# dbg-ram-4x8K.net
KiCad netlist of a schematic drawn in EAGLE
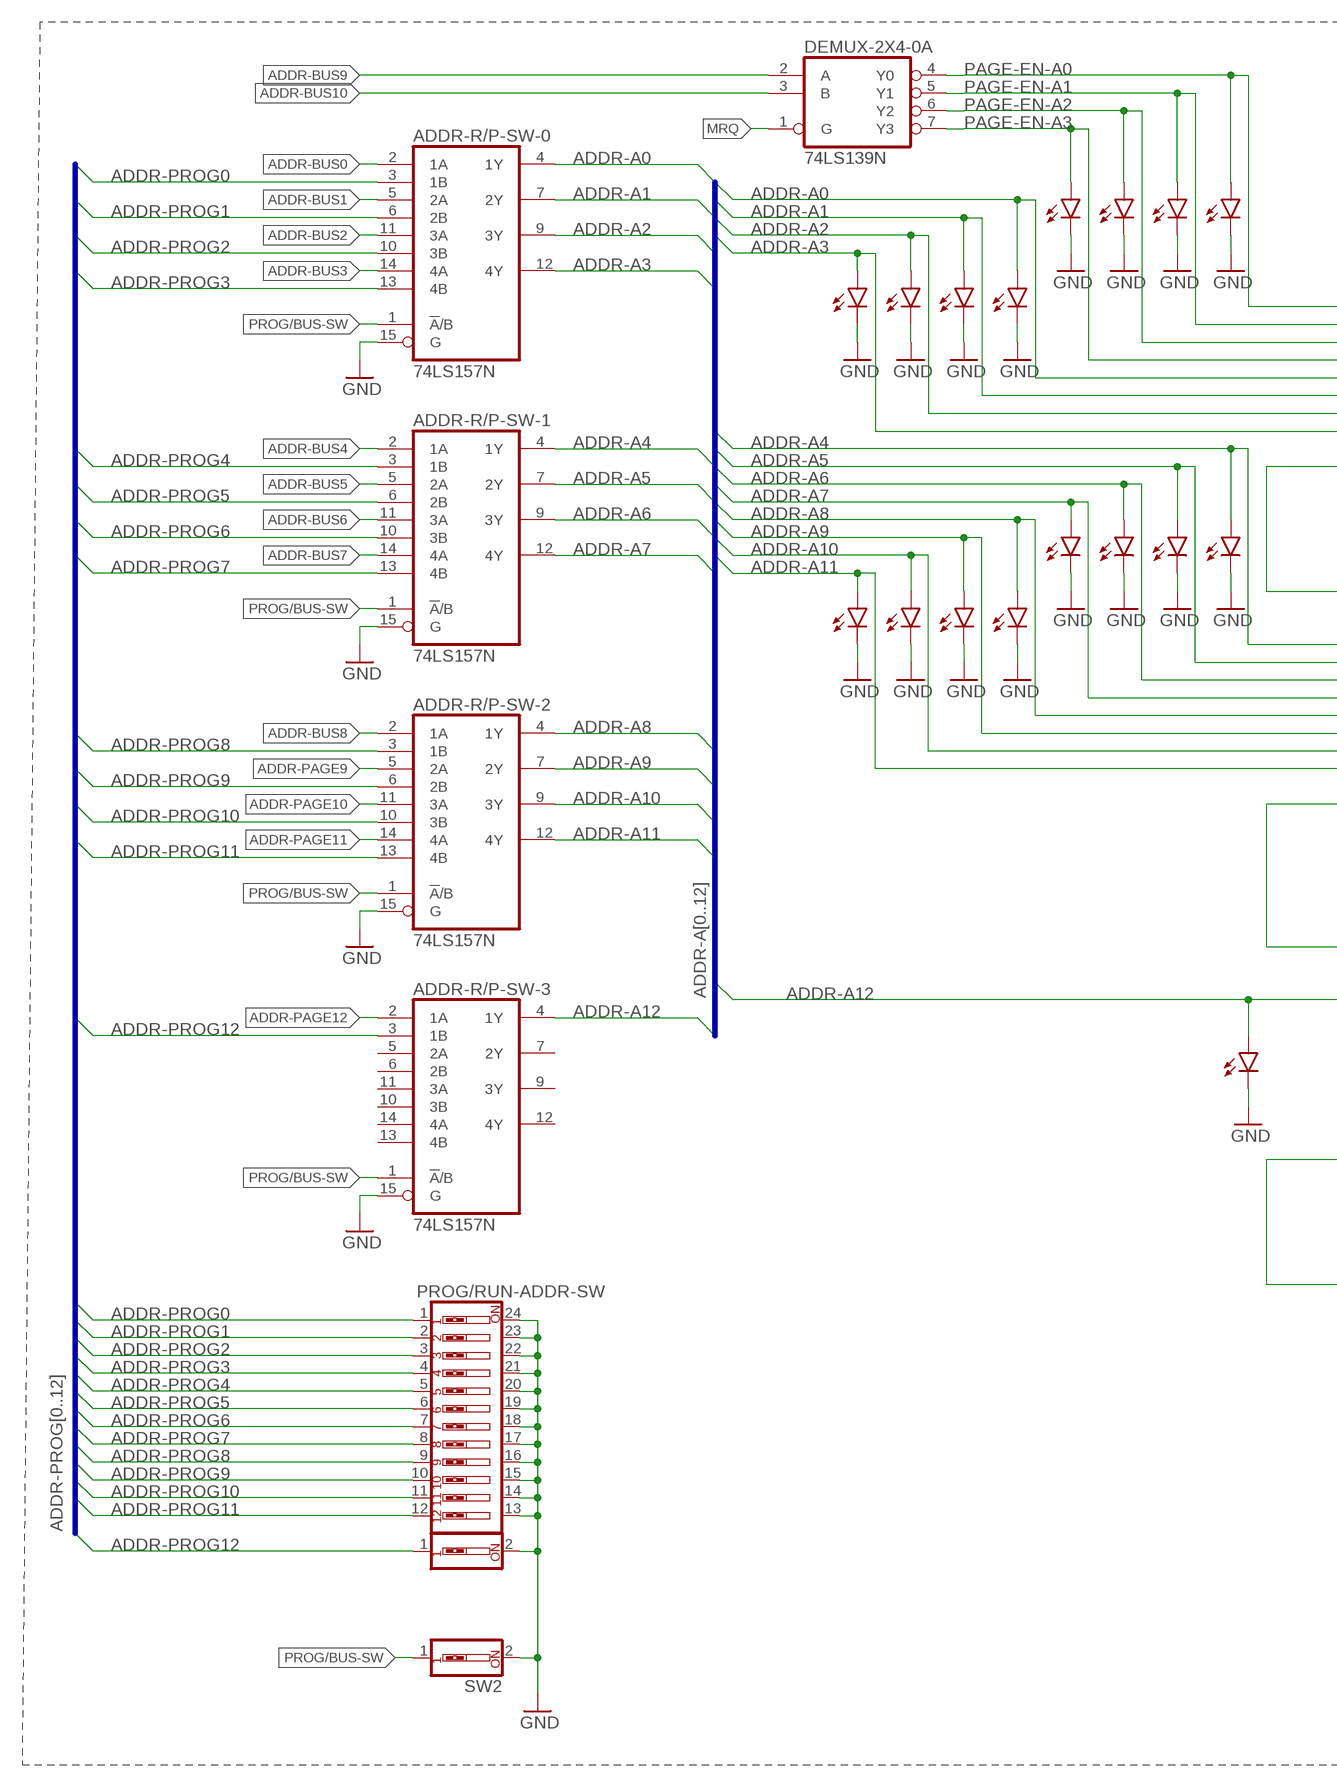
[diagram p0: schematic, sheet 1, part 1 of 2]
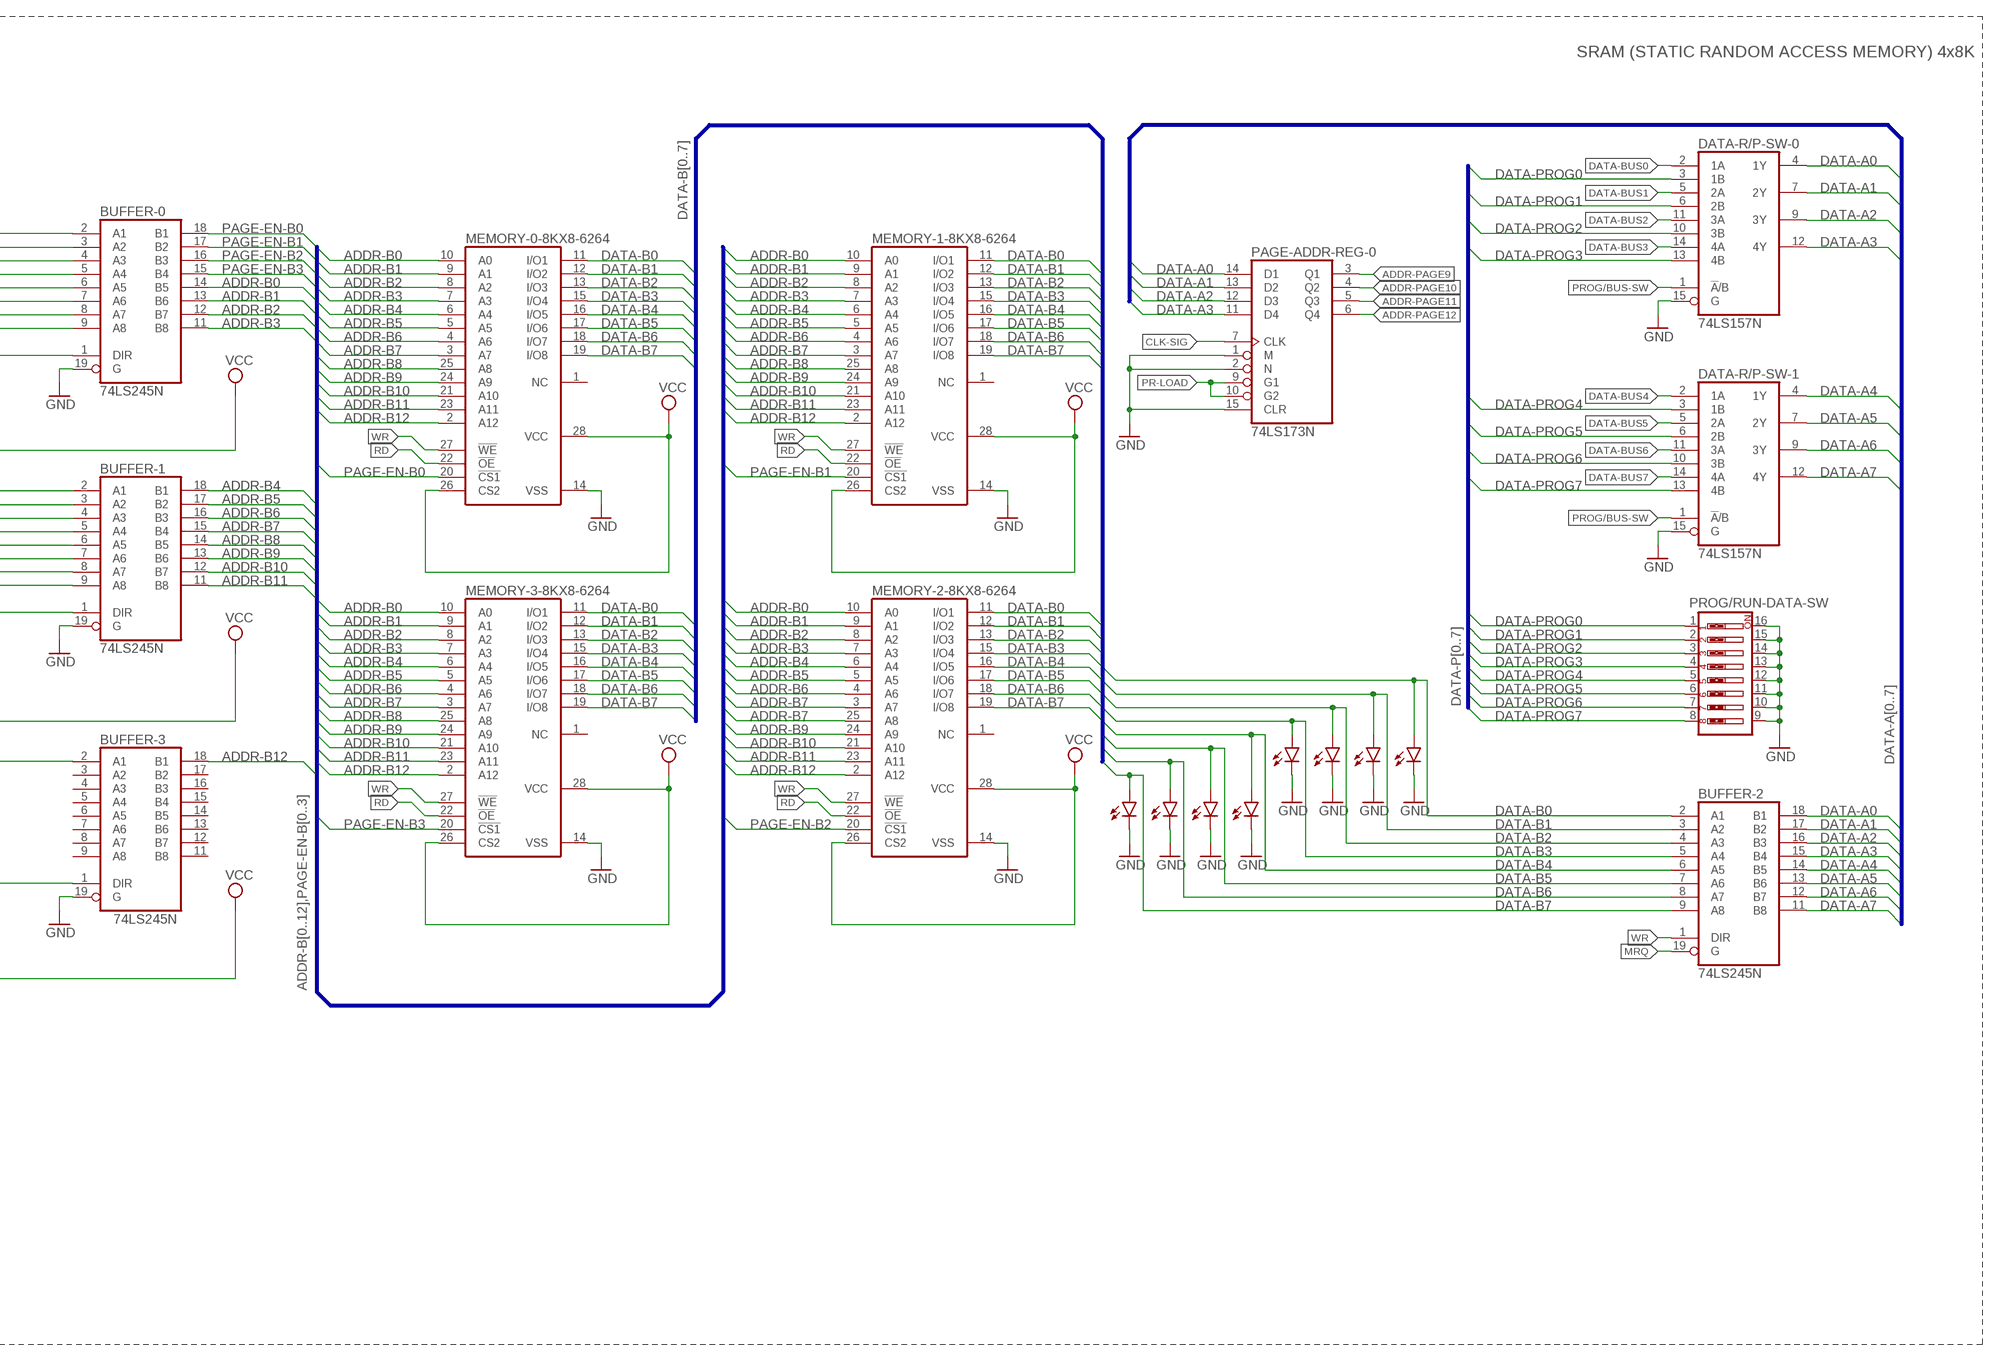
[diagram p1: schematic, sheet 1, part 2 of 2]

(export (version "E")
  (design (tool "Eeschema 10.0.6"))
  (components
    (comp (ref "ADDR-R/P-SW-0")
      (value "74LS157N")
      (footprint "eagle-import:DIL16")
      (libsource (lib "eagle-import") (part "74157NLS"))
    )
    (comp (ref "ADDR-R/P-SW-1")
      (value "74LS157N")
      (footprint "eagle-import:DIL16")
      (libsource (lib "eagle-import") (part "74157NLS"))
    )
    (comp (ref "ADDR-R/P-SW-2")
      (value "74LS157N")
      (footprint "eagle-import:DIL16")
      (libsource (lib "eagle-import") (part "74157NLS"))
    )
    (comp (ref "ADDR-R/P-SW-3")
      (value "74LS157N")
      (footprint "eagle-import:DIL16")
      (libsource (lib "eagle-import") (part "74157NLS"))
    )
    (comp (ref "BUFFER-0")
      (value "74LS245N")
      (footprint "eagle-import:DIL20")
      (libsource (lib "eagle-import") (part "74245NLS"))
    )
    (comp (ref "BUFFER-1")
      (value "74LS245N")
      (footprint "eagle-import:DIL20")
      (libsource (lib "eagle-import") (part "74245NLS"))
    )
    (comp (ref "BUFFER-2")
      (value "74LS245N")
      (footprint "eagle-import:DIL20")
      (libsource (lib "eagle-import") (part "74245NLS"))
    )
    (comp (ref "BUFFER-3")
      (value "74LS245N")
      (footprint "eagle-import:DIL20")
      (libsource (lib "eagle-import") (part "74245NLS"))
    )
    (comp (ref "DATA-R/P-SW-0")
      (value "74LS157N")
      (footprint "eagle-import:DIL16")
      (libsource (lib "eagle-import") (part "74157NLS"))
    )
    (comp (ref "DATA-R/P-SW-1")
      (value "74LS157N")
      (footprint "eagle-import:DIL16")
      (libsource (lib "eagle-import") (part "74157NLS"))
    )
    (comp (ref "DEMUX-2X4-0")
      (value "74LS139N")
      (footprint "eagle-import:DIL16")
      (libsource (lib "eagle-import") (part "74139NLS"))
    )
    (comp (ref "LED1")
      (value "LED5MM")
      (footprint "eagle-import:LED5MM")
      (libsource (lib "eagle-import") (part "LED5MM"))
    )
    (comp (ref "LED2")
      (value "LED5MM")
      (footprint "eagle-import:LED5MM")
      (libsource (lib "eagle-import") (part "LED5MM"))
    )
    (comp (ref "LED3")
      (value "LED5MM")
      (footprint "eagle-import:LED5MM")
      (libsource (lib "eagle-import") (part "LED5MM"))
    )
    (comp (ref "LED4")
      (value "LED5MM")
      (footprint "eagle-import:LED5MM")
      (libsource (lib "eagle-import") (part "LED5MM"))
    )
    (comp (ref "LED5")
      (value "LED5MM")
      (footprint "eagle-import:LED5MM")
      (libsource (lib "eagle-import") (part "LED5MM"))
    )
    (comp (ref "LED6")
      (value "LED5MM")
      (footprint "eagle-import:LED5MM")
      (libsource (lib "eagle-import") (part "LED5MM"))
    )
    (comp (ref "LED7")
      (value "LED5MM")
      (footprint "eagle-import:LED5MM")
      (libsource (lib "eagle-import") (part "LED5MM"))
    )
    (comp (ref "LED8")
      (value "LED5MM")
      (footprint "eagle-import:LED5MM")
      (libsource (lib "eagle-import") (part "LED5MM"))
    )
    (comp (ref "LED9")
      (value "LED5MM")
      (footprint "eagle-import:LED5MM")
      (libsource (lib "eagle-import") (part "LED5MM"))
    )
    (comp (ref "LED10")
      (value "LED5MM")
      (footprint "eagle-import:LED5MM")
      (libsource (lib "eagle-import") (part "LED5MM"))
    )
    (comp (ref "LED11")
      (value "LED5MM")
      (footprint "eagle-import:LED5MM")
      (libsource (lib "eagle-import") (part "LED5MM"))
    )
    (comp (ref "LED12")
      (value "LED5MM")
      (footprint "eagle-import:LED5MM")
      (libsource (lib "eagle-import") (part "LED5MM"))
    )
    (comp (ref "LED13")
      (value "LED5MM")
      (footprint "eagle-import:LED5MM")
      (libsource (lib "eagle-import") (part "LED5MM"))
    )
    (comp (ref "LED14")
      (value "LED5MM")
      (footprint "eagle-import:LED5MM")
      (libsource (lib "eagle-import") (part "LED5MM"))
    )
    (comp (ref "LED15")
      (value "LED5MM")
      (footprint "eagle-import:LED5MM")
      (libsource (lib "eagle-import") (part "LED5MM"))
    )
    (comp (ref "LED16")
      (value "LED5MM")
      (footprint "eagle-import:LED5MM")
      (libsource (lib "eagle-import") (part "LED5MM"))
    )
    (comp (ref "LED17")
      (value "LED5MM")
      (footprint "eagle-import:LED5MM")
      (libsource (lib "eagle-import") (part "LED5MM"))
    )
    (comp (ref "LED18")
      (value "LED5MM")
      (footprint "eagle-import:LED5MM")
      (libsource (lib "eagle-import") (part "LED5MM"))
    )
    (comp (ref "LED19")
      (value "LED5MM")
      (footprint "eagle-import:LED5MM")
      (libsource (lib "eagle-import") (part "LED5MM"))
    )
    (comp (ref "LED20")
      (value "LED5MM")
      (footprint "eagle-import:LED5MM")
      (libsource (lib "eagle-import") (part "LED5MM"))
    )
    (comp (ref "LED21")
      (value "LED5MM")
      (footprint "eagle-import:LED5MM")
      (libsource (lib "eagle-import") (part "LED5MM"))
    )
    (comp (ref "LED22")
      (value "LED5MM")
      (footprint "eagle-import:LED5MM")
      (libsource (lib "eagle-import") (part "LED5MM"))
    )
    (comp (ref "LED23")
      (value "LED5MM")
      (footprint "eagle-import:LED5MM")
      (libsource (lib "eagle-import") (part "LED5MM"))
    )
    (comp (ref "LED24")
      (value "LED5MM")
      (footprint "eagle-import:LED5MM")
      (libsource (lib "eagle-import") (part "LED5MM"))
    )
    (comp (ref "LED25")
      (value "LED5MM")
      (footprint "eagle-import:LED5MM")
      (libsource (lib "eagle-import") (part "LED5MM"))
    )
    (comp (ref "MEMORY-0-8KX8-6264")
      (value "6264A")
      (footprint "eagle-import:DIL28-6")
      (libsource (lib "eagle-import") (part "6264A"))
    )
    (comp (ref "MEMORY-1-8KX8-6264")
      (value "6264A")
      (footprint "eagle-import:DIL28-6")
      (libsource (lib "eagle-import") (part "6264A"))
    )
    (comp (ref "MEMORY-2-8KX8-6264")
      (value "6264A")
      (footprint "eagle-import:DIL28-6")
      (libsource (lib "eagle-import") (part "6264A"))
    )
    (comp (ref "MEMORY-3-8KX8-6264")
      (value "6264A")
      (footprint "eagle-import:DIL28-6")
      (libsource (lib "eagle-import") (part "6264A"))
    )
    (comp (ref "PAGE-ADDR-REG-0")
      (value "74LS173N")
      (footprint "eagle-import:DIL16")
      (libsource (lib "eagle-import") (part "74173NLS"))
    )
    (comp (ref "PROG/RUN-ADDR-SW")
      (value "SW_DIP-12")
      (footprint "eagle-import:EDG-12")
      (libsource (lib "eagle-import") (part "SW_DIP-12"))
    )
    (comp (ref "PROG/RUN-DATA-SW")
      (value "SW_DIP-8")
      (footprint "eagle-import:EDG-08")
      (libsource (lib "eagle-import") (part "SW_DIP-8"))
    )
    (comp (ref "SW2")
      (value "SW_DIP-1")
      (footprint "eagle-import:EDG-01")
      (libsource (lib "eagle-import") (part "SW_DIP-1"))
    )
    (comp (ref "SW3")
      (value "SW_DIP-1")
      (footprint "eagle-import:EDG-01")
      (libsource (lib "eagle-import") (part "SW_DIP-1"))
    )
  )
  (nets
    (net (code "9") (name "/ADDR-A0") (class "Default")
      (node (ref "ADDR-R/P-SW-0") (pin "4") (pinfunction "1Y_4") (pintype "output"))
      (node (ref "BUFFER-0") (pin "6") (pinfunction "A5_6") (pintype "bidirectional"))
      (node (ref "LED1") (pin "A") (pinfunction "A_A") (pintype "passive"))
    )
    (net (code "10") (name "/ADDR-A1") (class "Default")
      (node (ref "ADDR-R/P-SW-0") (pin "7") (pinfunction "2Y_7") (pintype "output"))
      (node (ref "BUFFER-0") (pin "7") (pinfunction "A6_7") (pintype "bidirectional"))
      (node (ref "LED2") (pin "A") (pinfunction "A_A") (pintype "passive"))
    )
    (net (code "11") (name "/ADDR-A2") (class "Default")
      (node (ref "ADDR-R/P-SW-0") (pin "9") (pinfunction "3Y_9") (pintype "output"))
      (node (ref "BUFFER-0") (pin "8") (pinfunction "A7_8") (pintype "bidirectional"))
      (node (ref "LED3") (pin "A") (pinfunction "A_A") (pintype "passive"))
    )
    (net (code "12") (name "/ADDR-A3") (class "Default")
      (node (ref "ADDR-R/P-SW-0") (pin "12") (pinfunction "4Y_12") (pintype "output"))
      (node (ref "BUFFER-0") (pin "9") (pinfunction "A8_9") (pintype "bidirectional"))
      (node (ref "LED4") (pin "A") (pinfunction "A_A") (pintype "passive"))
    )
    (net (code "13") (name "/ADDR-A4") (class "Default")
      (node (ref "ADDR-R/P-SW-1") (pin "4") (pinfunction "1Y_4") (pintype "output"))
      (node (ref "BUFFER-1") (pin "2") (pinfunction "A1_2") (pintype "bidirectional"))
      (node (ref "LED5") (pin "A") (pinfunction "A_A") (pintype "passive"))
    )
    (net (code "14") (name "/ADDR-A5") (class "Default")
      (node (ref "ADDR-R/P-SW-1") (pin "7") (pinfunction "2Y_7") (pintype "output"))
      (node (ref "BUFFER-1") (pin "3") (pinfunction "A2_3") (pintype "bidirectional"))
      (node (ref "LED6") (pin "A") (pinfunction "A_A") (pintype "passive"))
    )
    (net (code "15") (name "/ADDR-A6") (class "Default")
      (node (ref "ADDR-R/P-SW-1") (pin "9") (pinfunction "3Y_9") (pintype "output"))
      (node (ref "BUFFER-1") (pin "4") (pinfunction "A3_4") (pintype "bidirectional"))
      (node (ref "LED10") (pin "A") (pinfunction "A_A") (pintype "passive"))
    )
    (net (code "16") (name "/ADDR-A7") (class "Default")
      (node (ref "ADDR-R/P-SW-1") (pin "12") (pinfunction "4Y_12") (pintype "output"))
      (node (ref "BUFFER-1") (pin "5") (pinfunction "A4_5") (pintype "bidirectional"))
      (node (ref "LED7") (pin "A") (pinfunction "A_A") (pintype "passive"))
    )
    (net (code "17") (name "/ADDR-A8") (class "Default")
      (node (ref "ADDR-R/P-SW-2") (pin "4") (pinfunction "1Y_4") (pintype "output"))
      (node (ref "BUFFER-1") (pin "6") (pinfunction "A5_6") (pintype "bidirectional"))
      (node (ref "LED8") (pin "A") (pinfunction "A_A") (pintype "passive"))
    )
    (net (code "18") (name "/ADDR-A9") (class "Default")
      (node (ref "ADDR-R/P-SW-2") (pin "7") (pinfunction "2Y_7") (pintype "output"))
      (node (ref "BUFFER-1") (pin "7") (pinfunction "A6_7") (pintype "bidirectional"))
      (node (ref "LED9") (pin "A") (pinfunction "A_A") (pintype "passive"))
    )
    (net (code "19") (name "/ADDR-A10") (class "Default")
      (node (ref "ADDR-R/P-SW-2") (pin "9") (pinfunction "3Y_9") (pintype "output"))
      (node (ref "BUFFER-1") (pin "8") (pinfunction "A7_8") (pintype "bidirectional"))
      (node (ref "LED15") (pin "A") (pinfunction "A_A") (pintype "passive"))
    )
    (net (code "20") (name "/ADDR-A11") (class "Default")
      (node (ref "ADDR-R/P-SW-2") (pin "12") (pinfunction "4Y_12") (pintype "output"))
      (node (ref "BUFFER-1") (pin "9") (pinfunction "A8_9") (pintype "bidirectional"))
      (node (ref "LED17") (pin "A") (pinfunction "A_A") (pintype "passive"))
    )
    (net (code "21") (name "/ADDR-A12") (class "Default")
      (node (ref "ADDR-R/P-SW-3") (pin "4") (pinfunction "1Y_4") (pintype "output"))
      (node (ref "BUFFER-3") (pin "2") (pinfunction "A1_2") (pintype "bidirectional"))
      (node (ref "LED16") (pin "A") (pinfunction "A_A") (pintype "passive"))
    )
    (net (code "23") (name "/ADDR-B0") (class "Default")
      (node (ref "BUFFER-0") (pin "14") (pinfunction "B5_14") (pintype "bidirectional"))
      (node (ref "MEMORY-0-8KX8-6264") (pin "10") (pinfunction "A0_10") (pintype "input"))
      (node (ref "MEMORY-1-8KX8-6264") (pin "10") (pinfunction "A0_10") (pintype "input"))
      (node (ref "MEMORY-2-8KX8-6264") (pin "10") (pinfunction "A0_10") (pintype "input"))
      (node (ref "MEMORY-3-8KX8-6264") (pin "10") (pinfunction "A0_10") (pintype "input"))
    )
    (net (code "24") (name "/ADDR-B1") (class "Default")
      (node (ref "BUFFER-0") (pin "13") (pinfunction "B6_13") (pintype "bidirectional"))
      (node (ref "MEMORY-0-8KX8-6264") (pin "9") (pinfunction "A1_9") (pintype "input"))
      (node (ref "MEMORY-1-8KX8-6264") (pin "9") (pinfunction "A1_9") (pintype "input"))
      (node (ref "MEMORY-2-8KX8-6264") (pin "9") (pinfunction "A1_9") (pintype "input"))
      (node (ref "MEMORY-3-8KX8-6264") (pin "9") (pinfunction "A1_9") (pintype "input"))
    )
    (net (code "25") (name "/ADDR-B2") (class "Default")
      (node (ref "BUFFER-0") (pin "12") (pinfunction "B7_12") (pintype "bidirectional"))
      (node (ref "MEMORY-0-8KX8-6264") (pin "8") (pinfunction "A2_8") (pintype "input"))
      (node (ref "MEMORY-1-8KX8-6264") (pin "8") (pinfunction "A2_8") (pintype "input"))
      (node (ref "MEMORY-2-8KX8-6264") (pin "8") (pinfunction "A2_8") (pintype "input"))
      (node (ref "MEMORY-3-8KX8-6264") (pin "8") (pinfunction "A2_8") (pintype "input"))
    )
    (net (code "26") (name "/ADDR-B3") (class "Default")
      (node (ref "BUFFER-0") (pin "11") (pinfunction "B8_11") (pintype "bidirectional"))
      (node (ref "MEMORY-0-8KX8-6264") (pin "7") (pinfunction "A3_7") (pintype "input"))
      (node (ref "MEMORY-1-8KX8-6264") (pin "7") (pinfunction "A3_7") (pintype "input"))
      (node (ref "MEMORY-2-8KX8-6264") (pin "7") (pinfunction "A3_7") (pintype "input"))
      (node (ref "MEMORY-3-8KX8-6264") (pin "7") (pinfunction "A3_7") (pintype "input"))
    )
    (net (code "27") (name "/ADDR-B4") (class "Default")
      (node (ref "BUFFER-1") (pin "18") (pinfunction "B1_18") (pintype "bidirectional"))
      (node (ref "MEMORY-0-8KX8-6264") (pin "6") (pinfunction "A4_6") (pintype "input"))
      (node (ref "MEMORY-1-8KX8-6264") (pin "6") (pinfunction "A4_6") (pintype "input"))
      (node (ref "MEMORY-2-8KX8-6264") (pin "6") (pinfunction "A4_6") (pintype "input"))
      (node (ref "MEMORY-3-8KX8-6264") (pin "6") (pinfunction "A4_6") (pintype "input"))
    )
    (net (code "28") (name "/ADDR-B5") (class "Default")
      (node (ref "BUFFER-1") (pin "17") (pinfunction "B2_17") (pintype "bidirectional"))
      (node (ref "MEMORY-0-8KX8-6264") (pin "5") (pinfunction "A5_5") (pintype "input"))
      (node (ref "MEMORY-1-8KX8-6264") (pin "5") (pinfunction "A5_5") (pintype "input"))
      (node (ref "MEMORY-2-8KX8-6264") (pin "5") (pinfunction "A5_5") (pintype "input"))
      (node (ref "MEMORY-3-8KX8-6264") (pin "5") (pinfunction "A5_5") (pintype "input"))
    )
    (net (code "29") (name "/ADDR-B6") (class "Default")
      (node (ref "BUFFER-1") (pin "16") (pinfunction "B3_16") (pintype "bidirectional"))
      (node (ref "MEMORY-0-8KX8-6264") (pin "4") (pinfunction "A6_4") (pintype "input"))
      (node (ref "MEMORY-1-8KX8-6264") (pin "4") (pinfunction "A6_4") (pintype "input"))
      (node (ref "MEMORY-2-8KX8-6264") (pin "4") (pinfunction "A6_4") (pintype "input"))
      (node (ref "MEMORY-3-8KX8-6264") (pin "4") (pinfunction "A6_4") (pintype "input"))
    )
    (net (code "30") (name "/ADDR-B7") (class "Default")
      (node (ref "BUFFER-1") (pin "15") (pinfunction "B4_15") (pintype "bidirectional"))
      (node (ref "MEMORY-0-8KX8-6264") (pin "3") (pinfunction "A7_3") (pintype "input"))
      (node (ref "MEMORY-1-8KX8-6264") (pin "3") (pinfunction "A7_3") (pintype "input"))
      (node (ref "MEMORY-2-8KX8-6264") (pin "25") (pinfunction "A8_25") (pintype "input"))
      (node (ref "MEMORY-2-8KX8-6264") (pin "3") (pinfunction "A7_3") (pintype "input"))
      (node (ref "MEMORY-3-8KX8-6264") (pin "3") (pinfunction "A7_3") (pintype "input"))
    )
    (net (code "31") (name "/ADDR-B8") (class "Default")
      (node (ref "BUFFER-1") (pin "14") (pinfunction "B5_14") (pintype "bidirectional"))
      (node (ref "MEMORY-0-8KX8-6264") (pin "25") (pinfunction "A8_25") (pintype "input"))
      (node (ref "MEMORY-1-8KX8-6264") (pin "25") (pinfunction "A8_25") (pintype "input"))
      (node (ref "MEMORY-3-8KX8-6264") (pin "25") (pinfunction "A8_25") (pintype "input"))
    )
    (net (code "32") (name "/ADDR-B9") (class "Default")
      (node (ref "BUFFER-1") (pin "13") (pinfunction "B6_13") (pintype "bidirectional"))
      (node (ref "MEMORY-0-8KX8-6264") (pin "24") (pinfunction "A9_24") (pintype "input"))
      (node (ref "MEMORY-1-8KX8-6264") (pin "24") (pinfunction "A9_24") (pintype "input"))
      (node (ref "MEMORY-2-8KX8-6264") (pin "24") (pinfunction "A9_24") (pintype "input"))
      (node (ref "MEMORY-3-8KX8-6264") (pin "24") (pinfunction "A9_24") (pintype "input"))
    )
    (net (code "33") (name "/ADDR-B10") (class "Default")
      (node (ref "BUFFER-1") (pin "12") (pinfunction "B7_12") (pintype "bidirectional"))
      (node (ref "MEMORY-0-8KX8-6264") (pin "21") (pinfunction "A10_21") (pintype "input"))
      (node (ref "MEMORY-1-8KX8-6264") (pin "21") (pinfunction "A10_21") (pintype "input"))
      (node (ref "MEMORY-2-8KX8-6264") (pin "21") (pinfunction "A10_21") (pintype "input"))
      (node (ref "MEMORY-3-8KX8-6264") (pin "21") (pinfunction "A10_21") (pintype "input"))
    )
    (net (code "34") (name "/ADDR-B11") (class "Default")
      (node (ref "BUFFER-1") (pin "11") (pinfunction "B8_11") (pintype "bidirectional"))
      (node (ref "MEMORY-0-8KX8-6264") (pin "23") (pinfunction "A11_23") (pintype "input"))
      (node (ref "MEMORY-1-8KX8-6264") (pin "23") (pinfunction "A11_23") (pintype "input"))
      (node (ref "MEMORY-2-8KX8-6264") (pin "23") (pinfunction "A11_23") (pintype "input"))
      (node (ref "MEMORY-3-8KX8-6264") (pin "23") (pinfunction "A11_23") (pintype "input"))
    )
    (net (code "35") (name "/ADDR-B12") (class "Default")
      (node (ref "BUFFER-3") (pin "18") (pinfunction "B1_18") (pintype "bidirectional"))
      (node (ref "MEMORY-0-8KX8-6264") (pin "2") (pinfunction "A12_2") (pintype "input"))
      (node (ref "MEMORY-1-8KX8-6264") (pin "2") (pinfunction "A12_2") (pintype "input"))
      (node (ref "MEMORY-2-8KX8-6264") (pin "2") (pinfunction "A12_2") (pintype "input"))
      (node (ref "MEMORY-3-8KX8-6264") (pin "2") (pinfunction "A12_2") (pintype "input"))
    )
    (net (code "36") (name "/ADDR-PROG0") (class "Default")
      (node (ref "ADDR-R/P-SW-0") (pin "3") (pinfunction "1B_3") (pintype "input"))
      (node (ref "PROG/RUN-ADDR-SW") (pin "1") (pinfunction "1_1") (pintype "passive"))
    )
    (net (code "37") (name "/ADDR-PROG1") (class "Default")
      (node (ref "ADDR-R/P-SW-0") (pin "6") (pinfunction "2B_6") (pintype "input"))
      (node (ref "PROG/RUN-ADDR-SW") (pin "2") (pinfunction "2_2") (pintype "passive"))
    )
    (net (code "38") (name "/ADDR-PROG2") (class "Default")
      (node (ref "ADDR-R/P-SW-0") (pin "10") (pinfunction "3B_10") (pintype "input"))
      (node (ref "PROG/RUN-ADDR-SW") (pin "3") (pinfunction "3_3") (pintype "passive"))
    )
    (net (code "39") (name "/ADDR-PROG3") (class "Default")
      (node (ref "ADDR-R/P-SW-0") (pin "13") (pinfunction "4B_13") (pintype "input"))
      (node (ref "PROG/RUN-ADDR-SW") (pin "4") (pinfunction "4_4") (pintype "passive"))
    )
    (net (code "40") (name "/ADDR-PROG4") (class "Default")
      (node (ref "ADDR-R/P-SW-1") (pin "3") (pinfunction "1B_3") (pintype "input"))
      (node (ref "PROG/RUN-ADDR-SW") (pin "5") (pinfunction "5_5") (pintype "passive"))
    )
    (net (code "41") (name "/ADDR-PROG5") (class "Default")
      (node (ref "ADDR-R/P-SW-1") (pin "6") (pinfunction "2B_6") (pintype "input"))
      (node (ref "PROG/RUN-ADDR-SW") (pin "6") (pinfunction "6_6") (pintype "passive"))
    )
    (net (code "42") (name "/ADDR-PROG6") (class "Default")
      (node (ref "ADDR-R/P-SW-1") (pin "10") (pinfunction "3B_10") (pintype "input"))
      (node (ref "PROG/RUN-ADDR-SW") (pin "7") (pinfunction "7_7") (pintype "passive"))
    )
    (net (code "43") (name "/ADDR-PROG7") (class "Default")
      (node (ref "ADDR-R/P-SW-1") (pin "13") (pinfunction "4B_13") (pintype "input"))
      (node (ref "PROG/RUN-ADDR-SW") (pin "8") (pinfunction "8_8") (pintype "passive"))
    )
    (net (code "44") (name "/ADDR-PROG8") (class "Default")
      (node (ref "ADDR-R/P-SW-2") (pin "3") (pinfunction "1B_3") (pintype "input"))
      (node (ref "PROG/RUN-ADDR-SW") (pin "9") (pinfunction "9_9") (pintype "passive"))
    )
    (net (code "45") (name "/ADDR-PROG9") (class "Default")
      (node (ref "ADDR-R/P-SW-2") (pin "6") (pinfunction "2B_6") (pintype "input"))
      (node (ref "PROG/RUN-ADDR-SW") (pin "10") (pinfunction "10_10") (pintype "passive"))
    )
    (net (code "46") (name "/ADDR-PROG10") (class "Default")
      (node (ref "ADDR-R/P-SW-2") (pin "10") (pinfunction "3B_10") (pintype "input"))
      (node (ref "PROG/RUN-ADDR-SW") (pin "11") (pinfunction "11_11") (pintype "passive"))
    )
    (net (code "47") (name "/ADDR-PROG11") (class "Default")
      (node (ref "ADDR-R/P-SW-2") (pin "13") (pinfunction "4B_13") (pintype "input"))
      (node (ref "PROG/RUN-ADDR-SW") (pin "12") (pinfunction "12_12") (pintype "passive"))
    )
    (net (code "48") (name "/ADDR-PROG12") (class "Default")
      (node (ref "ADDR-R/P-SW-3") (pin "3") (pinfunction "1B_3") (pintype "input"))
      (node (ref "SW3") (pin "1") (pinfunction "1_1") (pintype "passive"))
    )
    (net (code "50") (name "/DATA-A0") (class "Default")
      (node (ref "BUFFER-2") (pin "18") (pinfunction "B1_18") (pintype "bidirectional"))
      (node (ref "DATA-R/P-SW-0") (pin "4") (pinfunction "1Y_4") (pintype "output"))
      (node (ref "PAGE-ADDR-REG-0") (pin "14") (pinfunction "D1_14") (pintype "input"))
    )
    (net (code "51") (name "/DATA-A1") (class "Default")
      (node (ref "BUFFER-2") (pin "17") (pinfunction "B2_17") (pintype "bidirectional"))
      (node (ref "DATA-R/P-SW-0") (pin "7") (pinfunction "2Y_7") (pintype "output"))
      (node (ref "PAGE-ADDR-REG-0") (pin "13") (pinfunction "D2_13") (pintype "input"))
    )
    (net (code "52") (name "/DATA-A2") (class "Default")
      (node (ref "BUFFER-2") (pin "16") (pinfunction "B3_16") (pintype "bidirectional"))
      (node (ref "DATA-R/P-SW-0") (pin "9") (pinfunction "3Y_9") (pintype "output"))
      (node (ref "PAGE-ADDR-REG-0") (pin "12") (pinfunction "D3_12") (pintype "input"))
    )
    (net (code "53") (name "/DATA-A3") (class "Default")
      (node (ref "BUFFER-2") (pin "15") (pinfunction "B4_15") (pintype "bidirectional"))
      (node (ref "DATA-R/P-SW-0") (pin "12") (pinfunction "4Y_12") (pintype "output"))
      (node (ref "PAGE-ADDR-REG-0") (pin "11") (pinfunction "D4_11") (pintype "input"))
    )
    (net (code "54") (name "/DATA-A4") (class "Default")
      (node (ref "BUFFER-2") (pin "14") (pinfunction "B5_14") (pintype "bidirectional"))
      (node (ref "DATA-R/P-SW-1") (pin "4") (pinfunction "1Y_4") (pintype "output"))
    )
    (net (code "55") (name "/DATA-A5") (class "Default")
      (node (ref "BUFFER-2") (pin "13") (pinfunction "B6_13") (pintype "bidirectional"))
      (node (ref "DATA-R/P-SW-1") (pin "7") (pinfunction "2Y_7") (pintype "output"))
    )
    (net (code "56") (name "/DATA-A6") (class "Default")
      (node (ref "BUFFER-2") (pin "12") (pinfunction "B7_12") (pintype "bidirectional"))
      (node (ref "DATA-R/P-SW-1") (pin "9") (pinfunction "3Y_9") (pintype "output"))
    )
    (net (code "57") (name "/DATA-A7") (class "Default")
      (node (ref "BUFFER-2") (pin "11") (pinfunction "B8_11") (pintype "bidirectional"))
      (node (ref "DATA-R/P-SW-1") (pin "12") (pinfunction "4Y_12") (pintype "output"))
    )
    (net (code "59") (name "/DATA-B0") (class "Default")
      (node (ref "BUFFER-2") (pin "2") (pinfunction "A1_2") (pintype "bidirectional"))
      (node (ref "LED25") (pin "A") (pinfunction "A_A") (pintype "passive"))
      (node (ref "MEMORY-0-8KX8-6264") (pin "11") (pinfunction "I/O1_11") (pintype "bidirectional"))
      (node (ref "MEMORY-1-8KX8-6264") (pin "11") (pinfunction "I/O1_11") (pintype "bidirectional"))
      (node (ref "MEMORY-2-8KX8-6264") (pin "11") (pinfunction "I/O1_11") (pintype "bidirectional"))
      (node (ref "MEMORY-3-8KX8-6264") (pin "11") (pinfunction "I/O1_11") (pintype "bidirectional"))
    )
    (net (code "60") (name "/DATA-B1") (class "Default")
      (node (ref "BUFFER-2") (pin "3") (pinfunction "A2_3") (pintype "bidirectional"))
      (node (ref "LED24") (pin "A") (pinfunction "A_A") (pintype "passive"))
      (node (ref "MEMORY-0-8KX8-6264") (pin "12") (pinfunction "I/O2_12") (pintype "bidirectional"))
      (node (ref "MEMORY-1-8KX8-6264") (pin "12") (pinfunction "I/O2_12") (pintype "bidirectional"))
      (node (ref "MEMORY-2-8KX8-6264") (pin "12") (pinfunction "I/O2_12") (pintype "bidirectional"))
      (node (ref "MEMORY-3-8KX8-6264") (pin "12") (pinfunction "I/O2_12") (pintype "bidirectional"))
    )
    (net (code "61") (name "/DATA-B2") (class "Default")
      (node (ref "BUFFER-2") (pin "4") (pinfunction "A3_4") (pintype "bidirectional"))
      (node (ref "LED23") (pin "A") (pinfunction "A_A") (pintype "passive"))
      (node (ref "MEMORY-0-8KX8-6264") (pin "13") (pinfunction "I/O3_13") (pintype "bidirectional"))
      (node (ref "MEMORY-1-8KX8-6264") (pin "13") (pinfunction "I/O3_13") (pintype "bidirectional"))
      (node (ref "MEMORY-2-8KX8-6264") (pin "13") (pinfunction "I/O3_13") (pintype "bidirectional"))
      (node (ref "MEMORY-3-8KX8-6264") (pin "13") (pinfunction "I/O3_13") (pintype "bidirectional"))
    )
    (net (code "62") (name "/DATA-B3") (class "Default")
      (node (ref "BUFFER-2") (pin "5") (pinfunction "A4_5") (pintype "bidirectional"))
      (node (ref "LED22") (pin "A") (pinfunction "A_A") (pintype "passive"))
      (node (ref "MEMORY-0-8KX8-6264") (pin "15") (pinfunction "I/O4_15") (pintype "bidirectional"))
      (node (ref "MEMORY-1-8KX8-6264") (pin "15") (pinfunction "I/O4_15") (pintype "bidirectional"))
      (node (ref "MEMORY-2-8KX8-6264") (pin "15") (pinfunction "I/O4_15") (pintype "bidirectional"))
      (node (ref "MEMORY-3-8KX8-6264") (pin "15") (pinfunction "I/O4_15") (pintype "bidirectional"))
    )
    (net (code "63") (name "/DATA-B4") (class "Default")
      (node (ref "BUFFER-2") (pin "6") (pinfunction "A5_6") (pintype "bidirectional"))
      (node (ref "LED21") (pin "A") (pinfunction "A_A") (pintype "passive"))
      (node (ref "MEMORY-0-8KX8-6264") (pin "16") (pinfunction "I/O5_16") (pintype "bidirectional"))
      (node (ref "MEMORY-1-8KX8-6264") (pin "16") (pinfunction "I/O5_16") (pintype "bidirectional"))
      (node (ref "MEMORY-2-8KX8-6264") (pin "16") (pinfunction "I/O5_16") (pintype "bidirectional"))
      (node (ref "MEMORY-3-8KX8-6264") (pin "16") (pinfunction "I/O5_16") (pintype "bidirectional"))
    )
    (net (code "64") (name "/DATA-B5") (class "Default")
      (node (ref "BUFFER-2") (pin "7") (pinfunction "A6_7") (pintype "bidirectional"))
      (node (ref "LED20") (pin "A") (pinfunction "A_A") (pintype "passive"))
      (node (ref "MEMORY-0-8KX8-6264") (pin "17") (pinfunction "I/O6_17") (pintype "bidirectional"))
      (node (ref "MEMORY-1-8KX8-6264") (pin "17") (pinfunction "I/O6_17") (pintype "bidirectional"))
      (node (ref "MEMORY-2-8KX8-6264") (pin "17") (pinfunction "I/O6_17") (pintype "bidirectional"))
      (node (ref "MEMORY-3-8KX8-6264") (pin "17") (pinfunction "I/O6_17") (pintype "bidirectional"))
    )
    (net (code "65") (name "/DATA-B6") (class "Default")
      (node (ref "BUFFER-2") (pin "8") (pinfunction "A7_8") (pintype "bidirectional"))
      (node (ref "LED19") (pin "A") (pinfunction "A_A") (pintype "passive"))
      (node (ref "MEMORY-0-8KX8-6264") (pin "18") (pinfunction "I/O7_18") (pintype "bidirectional"))
      (node (ref "MEMORY-1-8KX8-6264") (pin "18") (pinfunction "I/O7_18") (pintype "bidirectional"))
      (node (ref "MEMORY-2-8KX8-6264") (pin "18") (pinfunction "I/O7_18") (pintype "bidirectional"))
      (node (ref "MEMORY-3-8KX8-6264") (pin "18") (pinfunction "I/O7_18") (pintype "bidirectional"))
    )
    (net (code "66") (name "/DATA-B7") (class "Default")
      (node (ref "BUFFER-2") (pin "9") (pinfunction "A8_9") (pintype "bidirectional"))
      (node (ref "LED18") (pin "A") (pinfunction "A_A") (pintype "passive"))
      (node (ref "MEMORY-0-8KX8-6264") (pin "19") (pinfunction "I/O8_19") (pintype "bidirectional"))
      (node (ref "MEMORY-1-8KX8-6264") (pin "19") (pinfunction "I/O8_19") (pintype "bidirectional"))
      (node (ref "MEMORY-2-8KX8-6264") (pin "19") (pinfunction "I/O8_19") (pintype "bidirectional"))
      (node (ref "MEMORY-3-8KX8-6264") (pin "19") (pinfunction "I/O8_19") (pintype "bidirectional"))
    )
    (net (code "68") (name "/DATA-PROG0") (class "Default")
      (node (ref "DATA-R/P-SW-0") (pin "3") (pinfunction "1B_3") (pintype "input"))
      (node (ref "PROG/RUN-DATA-SW") (pin "1") (pinfunction "1_1") (pintype "passive"))
    )
    (net (code "69") (name "/DATA-PROG1") (class "Default")
      (node (ref "DATA-R/P-SW-0") (pin "6") (pinfunction "2B_6") (pintype "input"))
      (node (ref "PROG/RUN-DATA-SW") (pin "2") (pinfunction "2_2") (pintype "passive"))
    )
    (net (code "70") (name "/DATA-PROG2") (class "Default")
      (node (ref "DATA-R/P-SW-0") (pin "10") (pinfunction "3B_10") (pintype "input"))
      (node (ref "PROG/RUN-DATA-SW") (pin "3") (pinfunction "3_3") (pintype "passive"))
    )
    (net (code "71") (name "/DATA-PROG3") (class "Default")
      (node (ref "DATA-R/P-SW-0") (pin "13") (pinfunction "4B_13") (pintype "input"))
      (node (ref "PROG/RUN-DATA-SW") (pin "4") (pinfunction "4_4") (pintype "passive"))
    )
    (net (code "72") (name "/DATA-PROG4") (class "Default")
      (node (ref "DATA-R/P-SW-1") (pin "3") (pinfunction "1B_3") (pintype "input"))
      (node (ref "PROG/RUN-DATA-SW") (pin "5") (pinfunction "5_5") (pintype "passive"))
    )
    (net (code "73") (name "/DATA-PROG5") (class "Default")
      (node (ref "DATA-R/P-SW-1") (pin "6") (pinfunction "2B_6") (pintype "input"))
      (node (ref "PROG/RUN-DATA-SW") (pin "6") (pinfunction "6_6") (pintype "passive"))
    )
    (net (code "74") (name "/DATA-PROG6") (class "Default")
      (node (ref "DATA-R/P-SW-1") (pin "10") (pinfunction "3B_10") (pintype "input"))
      (node (ref "PROG/RUN-DATA-SW") (pin "7") (pinfunction "7_7") (pintype "passive"))
    )
    (net (code "75") (name "/DATA-PROG7") (class "Default")
      (node (ref "DATA-R/P-SW-1") (pin "13") (pinfunction "4B_13") (pintype "input"))
      (node (ref "PROG/RUN-DATA-SW") (pin "8") (pinfunction "8_8") (pintype "passive"))
    )
    (net (code "77") (name "/PAGE-EN-A0") (class "Default")
      (node (ref "BUFFER-0") (pin "2") (pinfunction "A1_2") (pintype "bidirectional"))
      (node (ref "DEMUX-2X4-0") (pin "4") (pinfunction "Y0_4") (pintype "output"))
      (node (ref "LED11") (pin "A") (pinfunction "A_A") (pintype "passive"))
    )
    (net (code "78") (name "/PAGE-EN-A1") (class "Default")
      (node (ref "BUFFER-0") (pin "3") (pinfunction "A2_3") (pintype "bidirectional"))
      (node (ref "DEMUX-2X4-0") (pin "5") (pinfunction "Y1_5") (pintype "output"))
      (node (ref "LED12") (pin "A") (pinfunction "A_A") (pintype "passive"))
    )
    (net (code "79") (name "/PAGE-EN-A2") (class "Default")
      (node (ref "BUFFER-0") (pin "4") (pinfunction "A3_4") (pintype "bidirectional"))
      (node (ref "DEMUX-2X4-0") (pin "6") (pinfunction "Y2_6") (pintype "output"))
      (node (ref "LED13") (pin "A") (pinfunction "A_A") (pintype "passive"))
    )
    (net (code "80") (name "/PAGE-EN-A3") (class "Default")
      (node (ref "BUFFER-0") (pin "5") (pinfunction "A4_5") (pintype "bidirectional"))
      (node (ref "DEMUX-2X4-0") (pin "7") (pinfunction "Y3_7") (pintype "output"))
      (node (ref "LED14") (pin "A") (pinfunction "A_A") (pintype "passive"))
    )
    (net (code "81") (name "/PAGE-EN-B0") (class "Default")
      (node (ref "BUFFER-0") (pin "18") (pinfunction "B1_18") (pintype "bidirectional"))
      (node (ref "MEMORY-0-8KX8-6264") (pin "20") (pinfunction "~{CS1}_20") (pintype "input"))
    )
    (net (code "82") (name "/PAGE-EN-B1") (class "Default")
      (node (ref "BUFFER-0") (pin "17") (pinfunction "B2_17") (pintype "bidirectional"))
      (node (ref "MEMORY-1-8KX8-6264") (pin "20") (pinfunction "~{CS1}_20") (pintype "input"))
    )
    (net (code "83") (name "/PAGE-EN-B2") (class "Default")
      (node (ref "BUFFER-0") (pin "16") (pinfunction "B3_16") (pintype "bidirectional"))
      (node (ref "MEMORY-2-8KX8-6264") (pin "20") (pinfunction "~{CS1}_20") (pintype "input"))
    )
    (net (code "84") (name "/PAGE-EN-B3") (class "Default")
      (node (ref "BUFFER-0") (pin "15") (pinfunction "B4_15") (pintype "bidirectional"))
      (node (ref "MEMORY-3-8KX8-6264") (pin "20") (pinfunction "~{CS1}_20") (pintype "input"))
    )
    (net (code "86") (name "ADDR-BUS0") (class "Default")
      (node (ref "ADDR-R/P-SW-0") (pin "2") (pinfunction "1A_2") (pintype "input"))
    )
    (net (code "87") (name "ADDR-BUS1") (class "Default")
      (node (ref "ADDR-R/P-SW-0") (pin "5") (pinfunction "2A_5") (pintype "input"))
    )
    (net (code "88") (name "ADDR-BUS2") (class "Default")
      (node (ref "ADDR-R/P-SW-0") (pin "11") (pinfunction "3A_11") (pintype "input"))
    )
    (net (code "89") (name "ADDR-BUS3") (class "Default")
      (node (ref "ADDR-R/P-SW-0") (pin "14") (pinfunction "4A_14") (pintype "input"))
    )
    (net (code "90") (name "ADDR-BUS4") (class "Default")
      (node (ref "ADDR-R/P-SW-1") (pin "2") (pinfunction "1A_2") (pintype "input"))
    )
    (net (code "91") (name "ADDR-BUS5") (class "Default")
      (node (ref "ADDR-R/P-SW-1") (pin "5") (pinfunction "2A_5") (pintype "input"))
    )
    (net (code "92") (name "ADDR-BUS6") (class "Default")
      (node (ref "ADDR-R/P-SW-1") (pin "11") (pinfunction "3A_11") (pintype "input"))
    )
    (net (code "93") (name "ADDR-BUS7") (class "Default")
      (node (ref "ADDR-R/P-SW-1") (pin "14") (pinfunction "4A_14") (pintype "input"))
    )
    (net (code "94") (name "ADDR-BUS8") (class "Default")
      (node (ref "ADDR-R/P-SW-2") (pin "2") (pinfunction "1A_2") (pintype "input"))
    )
    (net (code "95") (name "ADDR-BUS9") (class "Default")
      (node (ref "DEMUX-2X4-0") (pin "2") (pinfunction "A_2") (pintype "input"))
    )
    (net (code "96") (name "ADDR-BUS10") (class "Default")
      (node (ref "DEMUX-2X4-0") (pin "3") (pinfunction "B_3") (pintype "input"))
    )
    (net (code "97") (name "ADDR-PAGE9") (class "Default")
      (node (ref "ADDR-R/P-SW-2") (pin "5") (pinfunction "2A_5") (pintype "input"))
      (node (ref "PAGE-ADDR-REG-0") (pin "3") (pinfunction "Q1_3") (pintype "tri_state"))
    )
    (net (code "98") (name "ADDR-PAGE10") (class "Default")
      (node (ref "ADDR-R/P-SW-2") (pin "11") (pinfunction "3A_11") (pintype "input"))
      (node (ref "PAGE-ADDR-REG-0") (pin "4") (pinfunction "Q2_4") (pintype "tri_state"))
    )
    (net (code "99") (name "ADDR-PAGE11") (class "Default")
      (node (ref "ADDR-R/P-SW-2") (pin "14") (pinfunction "4A_14") (pintype "input"))
      (node (ref "PAGE-ADDR-REG-0") (pin "5") (pinfunction "Q3_5") (pintype "tri_state"))
    )
    (net (code "100") (name "ADDR-PAGE12") (class "Default")
      (node (ref "ADDR-R/P-SW-3") (pin "2") (pinfunction "1A_2") (pintype "input"))
      (node (ref "PAGE-ADDR-REG-0") (pin "6") (pinfunction "Q4_6") (pintype "tri_state"))
    )
    (net (code "101") (name "CLK-SIG") (class "Default")
      (node (ref "PAGE-ADDR-REG-0") (pin "7") (pinfunction "CLK_7") (pintype "input"))
    )
    (net (code "102") (name "DATA-BUS0") (class "Default")
      (node (ref "DATA-R/P-SW-0") (pin "2") (pinfunction "1A_2") (pintype "input"))
    )
    (net (code "103") (name "DATA-BUS1") (class "Default")
      (node (ref "DATA-R/P-SW-0") (pin "5") (pinfunction "2A_5") (pintype "input"))
    )
    (net (code "104") (name "DATA-BUS2") (class "Default")
      (node (ref "DATA-R/P-SW-0") (pin "11") (pinfunction "3A_11") (pintype "input"))
    )
    (net (code "105") (name "DATA-BUS3") (class "Default")
      (node (ref "DATA-R/P-SW-0") (pin "14") (pinfunction "4A_14") (pintype "input"))
    )
    (net (code "106") (name "DATA-BUS4") (class "Default")
      (node (ref "DATA-R/P-SW-1") (pin "2") (pinfunction "1A_2") (pintype "input"))
    )
    (net (code "107") (name "DATA-BUS5") (class "Default")
      (node (ref "DATA-R/P-SW-1") (pin "5") (pinfunction "2A_5") (pintype "input"))
    )
    (net (code "108") (name "DATA-BUS6") (class "Default")
      (node (ref "DATA-R/P-SW-1") (pin "11") (pinfunction "3A_11") (pintype "input"))
    )
    (net (code "109") (name "DATA-BUS7") (class "Default")
      (node (ref "DATA-R/P-SW-1") (pin "14") (pinfunction "4A_14") (pintype "input"))
    )
    (net (code "110") (name "GND") (class "Default")
      (node (ref "ADDR-R/P-SW-0") (pin "15") (pinfunction "G_15") (pintype "input"))
      (node (ref "ADDR-R/P-SW-1") (pin "15") (pinfunction "G_15") (pintype "input"))
      (node (ref "ADDR-R/P-SW-2") (pin "15") (pinfunction "G_15") (pintype "input"))
      (node (ref "ADDR-R/P-SW-3") (pin "15") (pinfunction "G_15") (pintype "input"))
      (node (ref "BUFFER-0") (pin "19") (pinfunction "G_19") (pintype "input"))
      (node (ref "BUFFER-1") (pin "19") (pinfunction "G_19") (pintype "input"))
      (node (ref "BUFFER-3") (pin "19") (pinfunction "G_19") (pintype "input"))
      (node (ref "DATA-R/P-SW-0") (pin "15") (pinfunction "G_15") (pintype "input"))
      (node (ref "DATA-R/P-SW-1") (pin "15") (pinfunction "G_15") (pintype "input"))
      (node (ref "LED1") (pin "K") (pinfunction "C_K") (pintype "passive"))
      (node (ref "LED10") (pin "K") (pinfunction "C_K") (pintype "passive"))
      (node (ref "LED11") (pin "K") (pinfunction "C_K") (pintype "passive"))
      (node (ref "LED12") (pin "K") (pinfunction "C_K") (pintype "passive"))
      (node (ref "LED13") (pin "K") (pinfunction "C_K") (pintype "passive"))
      (node (ref "LED14") (pin "K") (pinfunction "C_K") (pintype "passive"))
      (node (ref "LED15") (pin "K") (pinfunction "C_K") (pintype "passive"))
      (node (ref "LED16") (pin "K") (pinfunction "C_K") (pintype "passive"))
      (node (ref "LED17") (pin "K") (pinfunction "C_K") (pintype "passive"))
      (node (ref "LED18") (pin "K") (pinfunction "C_K") (pintype "passive"))
      (node (ref "LED19") (pin "K") (pinfunction "C_K") (pintype "passive"))
      (node (ref "LED2") (pin "K") (pinfunction "C_K") (pintype "passive"))
      (node (ref "LED20") (pin "K") (pinfunction "C_K") (pintype "passive"))
      (node (ref "LED21") (pin "K") (pinfunction "C_K") (pintype "passive"))
      (node (ref "LED22") (pin "K") (pinfunction "C_K") (pintype "passive"))
      (node (ref "LED23") (pin "K") (pinfunction "C_K") (pintype "passive"))
      (node (ref "LED24") (pin "K") (pinfunction "C_K") (pintype "passive"))
      (node (ref "LED25") (pin "K") (pinfunction "C_K") (pintype "passive"))
      (node (ref "LED3") (pin "K") (pinfunction "C_K") (pintype "passive"))
      (node (ref "LED4") (pin "K") (pinfunction "C_K") (pintype "passive"))
      (node (ref "LED5") (pin "K") (pinfunction "C_K") (pintype "passive"))
      (node (ref "LED6") (pin "K") (pinfunction "C_K") (pintype "passive"))
      (node (ref "LED7") (pin "K") (pinfunction "C_K") (pintype "passive"))
      (node (ref "LED8") (pin "K") (pinfunction "C_K") (pintype "passive"))
      (node (ref "LED9") (pin "K") (pinfunction "C_K") (pintype "passive"))
      (node (ref "MEMORY-0-8KX8-6264") (pin "14") (pinfunction "VSS_14") (pintype "power_in"))
      (node (ref "MEMORY-1-8KX8-6264") (pin "14") (pinfunction "VSS_14") (pintype "power_in"))
      (node (ref "MEMORY-2-8KX8-6264") (pin "14") (pinfunction "VSS_14") (pintype "power_in"))
      (node (ref "MEMORY-3-8KX8-6264") (pin "14") (pinfunction "VSS_14") (pintype "power_in"))
      (node (ref "PAGE-ADDR-REG-0") (pin "1") (pinfunction "M_1") (pintype "input"))
      (node (ref "PAGE-ADDR-REG-0") (pin "15") (pinfunction "CLR_15") (pintype "input"))
      (node (ref "PAGE-ADDR-REG-0") (pin "2") (pinfunction "N_2") (pintype "input"))
      (node (ref "PROG/RUN-ADDR-SW") (pin "13") (pinfunction "13_13") (pintype "passive"))
      (node (ref "PROG/RUN-ADDR-SW") (pin "14") (pinfunction "14_14") (pintype "passive"))
      (node (ref "PROG/RUN-ADDR-SW") (pin "15") (pinfunction "15_15") (pintype "passive"))
      (node (ref "PROG/RUN-ADDR-SW") (pin "16") (pinfunction "16_16") (pintype "passive"))
      (node (ref "PROG/RUN-ADDR-SW") (pin "17") (pinfunction "17_17") (pintype "passive"))
      (node (ref "PROG/RUN-ADDR-SW") (pin "18") (pinfunction "18_18") (pintype "passive"))
      (node (ref "PROG/RUN-ADDR-SW") (pin "19") (pinfunction "19_19") (pintype "passive"))
      (node (ref "PROG/RUN-ADDR-SW") (pin "20") (pinfunction "20_20") (pintype "passive"))
      (node (ref "PROG/RUN-ADDR-SW") (pin "21") (pinfunction "21_21") (pintype "passive"))
      (node (ref "PROG/RUN-ADDR-SW") (pin "22") (pinfunction "22_22") (pintype "passive"))
      (node (ref "PROG/RUN-ADDR-SW") (pin "23") (pinfunction "23_23") (pintype "passive"))
      (node (ref "PROG/RUN-ADDR-SW") (pin "24") (pinfunction "24_24") (pintype "passive"))
      (node (ref "PROG/RUN-DATA-SW") (pin "10") (pinfunction "10_10") (pintype "passive"))
      (node (ref "PROG/RUN-DATA-SW") (pin "11") (pinfunction "11_11") (pintype "passive"))
      (node (ref "PROG/RUN-DATA-SW") (pin "12") (pinfunction "12_12") (pintype "passive"))
      (node (ref "PROG/RUN-DATA-SW") (pin "13") (pinfunction "13_13") (pintype "passive"))
      (node (ref "PROG/RUN-DATA-SW") (pin "14") (pinfunction "14_14") (pintype "passive"))
      (node (ref "PROG/RUN-DATA-SW") (pin "15") (pinfunction "15_15") (pintype "passive"))
      (node (ref "PROG/RUN-DATA-SW") (pin "16") (pinfunction "16_16") (pintype "passive"))
      (node (ref "PROG/RUN-DATA-SW") (pin "9") (pinfunction "9_9") (pintype "passive"))
      (node (ref "SW2") (pin "2") (pinfunction "2_2") (pintype "passive"))
      (node (ref "SW3") (pin "2") (pinfunction "2_2") (pintype "passive"))
    )
    (net (code "111") (name "MRQ") (class "Default")
      (node (ref "BUFFER-2") (pin "19") (pinfunction "G_19") (pintype "input"))
      (node (ref "DEMUX-2X4-0") (pin "1") (pinfunction "G_1") (pintype "input"))
    )
    (net (code "112") (name "PR-LOAD") (class "Default")
      (node (ref "PAGE-ADDR-REG-0") (pin "10") (pinfunction "G2_10") (pintype "input"))
      (node (ref "PAGE-ADDR-REG-0") (pin "9") (pinfunction "G1_9") (pintype "input"))
    )
    (net (code "113") (name "PROG{slash}BUS-SW") (class "Default")
      (node (ref "ADDR-R/P-SW-0") (pin "1") (pinfunction "~{A}/B_1") (pintype "input"))
      (node (ref "ADDR-R/P-SW-1") (pin "1") (pinfunction "~{A}/B_1") (pintype "input"))
      (node (ref "ADDR-R/P-SW-2") (pin "1") (pinfunction "~{A}/B_1") (pintype "input"))
      (node (ref "ADDR-R/P-SW-3") (pin "1") (pinfunction "~{A}/B_1") (pintype "input"))
      (node (ref "DATA-R/P-SW-0") (pin "1") (pinfunction "~{A}/B_1") (pintype "input"))
      (node (ref "DATA-R/P-SW-1") (pin "1") (pinfunction "~{A}/B_1") (pintype "input"))
      (node (ref "SW2") (pin "1") (pinfunction "1_1") (pintype "passive"))
    )
    (net (code "114") (name "RD") (class "Default")
      (node (ref "MEMORY-0-8KX8-6264") (pin "22") (pinfunction "~{OE}_22") (pintype "input"))
      (node (ref "MEMORY-1-8KX8-6264") (pin "22") (pinfunction "~{OE}_22") (pintype "input"))
      (node (ref "MEMORY-2-8KX8-6264") (pin "22") (pinfunction "~{OE}_22") (pintype "input"))
      (node (ref "MEMORY-3-8KX8-6264") (pin "22") (pinfunction "~{OE}_22") (pintype "input"))
    )
    (net (code "115") (name "VCC") (class "Default")
      (node (ref "BUFFER-0") (pin "1") (pinfunction "DIR_1") (pintype "input"))
      (node (ref "BUFFER-1") (pin "1") (pinfunction "DIR_1") (pintype "input"))
      (node (ref "BUFFER-3") (pin "1") (pinfunction "DIR_1") (pintype "input"))
      (node (ref "MEMORY-0-8KX8-6264") (pin "26") (pinfunction "CS2_26") (pintype "input"))
      (node (ref "MEMORY-0-8KX8-6264") (pin "28") (pinfunction "VCC_28") (pintype "power_in"))
      (node (ref "MEMORY-1-8KX8-6264") (pin "26") (pinfunction "CS2_26") (pintype "input"))
      (node (ref "MEMORY-1-8KX8-6264") (pin "28") (pinfunction "VCC_28") (pintype "power_in"))
      (node (ref "MEMORY-2-8KX8-6264") (pin "26") (pinfunction "CS2_26") (pintype "input"))
      (node (ref "MEMORY-2-8KX8-6264") (pin "28") (pinfunction "VCC_28") (pintype "power_in"))
      (node (ref "MEMORY-3-8KX8-6264") (pin "26") (pinfunction "CS2_26") (pintype "input"))
      (node (ref "MEMORY-3-8KX8-6264") (pin "28") (pinfunction "VCC_28") (pintype "power_in"))
    )
    (net (code "116") (name "WR") (class "Default")
      (node (ref "BUFFER-2") (pin "1") (pinfunction "DIR_1") (pintype "input"))
      (node (ref "MEMORY-0-8KX8-6264") (pin "27") (pinfunction "~{WE}_27") (pintype "input"))
      (node (ref "MEMORY-1-8KX8-6264") (pin "27") (pinfunction "~{WE}_27") (pintype "input"))
      (node (ref "MEMORY-2-8KX8-6264") (pin "27") (pinfunction "~{WE}_27") (pintype "input"))
      (node (ref "MEMORY-3-8KX8-6264") (pin "27") (pinfunction "~{WE}_27") (pintype "input"))
    )
    (net (code "117") (name "unconnected-(ADDR-R/P-SW-3A-2A-Pad5)") (class "Default")
      (node (ref "ADDR-R/P-SW-3") (pin "5") (pinfunction "2A_5") (pintype "input"))
    )
    (net (code "118") (name "unconnected-(ADDR-R/P-SW-3A-2B-Pad6)") (class "Default")
      (node (ref "ADDR-R/P-SW-3") (pin "6") (pinfunction "2B_6") (pintype "input"))
    )
    (net (code "119") (name "unconnected-(ADDR-R/P-SW-3A-2Y-Pad7)") (class "Default")
      (node (ref "ADDR-R/P-SW-3") (pin "7") (pinfunction "2Y_7") (pintype "output"))
    )
    (net (code "120") (name "unconnected-(ADDR-R/P-SW-3A-3A-Pad11)") (class "Default")
      (node (ref "ADDR-R/P-SW-3") (pin "11") (pinfunction "3A_11") (pintype "input"))
    )
    (net (code "121") (name "unconnected-(ADDR-R/P-SW-3A-3B-Pad10)") (class "Default")
      (node (ref "ADDR-R/P-SW-3") (pin "10") (pinfunction "3B_10") (pintype "input"))
    )
    (net (code "122") (name "unconnected-(ADDR-R/P-SW-3A-3Y-Pad9)") (class "Default")
      (node (ref "ADDR-R/P-SW-3") (pin "9") (pinfunction "3Y_9") (pintype "output"))
    )
    (net (code "123") (name "unconnected-(ADDR-R/P-SW-3A-4A-Pad14)") (class "Default")
      (node (ref "ADDR-R/P-SW-3") (pin "14") (pinfunction "4A_14") (pintype "input"))
    )
    (net (code "124") (name "unconnected-(ADDR-R/P-SW-3A-4B-Pad13)") (class "Default")
      (node (ref "ADDR-R/P-SW-3") (pin "13") (pinfunction "4B_13") (pintype "input"))
    )
    (net (code "125") (name "unconnected-(ADDR-R/P-SW-3A-4Y-Pad12)") (class "Default")
      (node (ref "ADDR-R/P-SW-3") (pin "12") (pinfunction "4Y_12") (pintype "output"))
    )
    (net (code "126") (name "unconnected-(BUFFER-3A-A2-Pad3)") (class "Default")
      (node (ref "BUFFER-3") (pin "3") (pinfunction "A2_3") (pintype "bidirectional"))
    )
    (net (code "127") (name "unconnected-(BUFFER-3A-A3-Pad4)") (class "Default")
      (node (ref "BUFFER-3") (pin "4") (pinfunction "A3_4") (pintype "bidirectional"))
    )
    (net (code "128") (name "unconnected-(BUFFER-3A-A4-Pad5)") (class "Default")
      (node (ref "BUFFER-3") (pin "5") (pinfunction "A4_5") (pintype "bidirectional"))
    )
    (net (code "129") (name "unconnected-(BUFFER-3A-A5-Pad6)") (class "Default")
      (node (ref "BUFFER-3") (pin "6") (pinfunction "A5_6") (pintype "bidirectional"))
    )
    (net (code "130") (name "unconnected-(BUFFER-3A-A6-Pad7)") (class "Default")
      (node (ref "BUFFER-3") (pin "7") (pinfunction "A6_7") (pintype "bidirectional"))
    )
    (net (code "131") (name "unconnected-(BUFFER-3A-A7-Pad8)") (class "Default")
      (node (ref "BUFFER-3") (pin "8") (pinfunction "A7_8") (pintype "bidirectional"))
    )
    (net (code "132") (name "unconnected-(BUFFER-3A-A8-Pad9)") (class "Default")
      (node (ref "BUFFER-3") (pin "9") (pinfunction "A8_9") (pintype "bidirectional"))
    )
    (net (code "133") (name "unconnected-(BUFFER-3A-B2-Pad17)") (class "Default")
      (node (ref "BUFFER-3") (pin "17") (pinfunction "B2_17") (pintype "bidirectional"))
    )
    (net (code "134") (name "unconnected-(BUFFER-3A-B3-Pad16)") (class "Default")
      (node (ref "BUFFER-3") (pin "16") (pinfunction "B3_16") (pintype "bidirectional"))
    )
    (net (code "135") (name "unconnected-(BUFFER-3A-B4-Pad15)") (class "Default")
      (node (ref "BUFFER-3") (pin "15") (pinfunction "B4_15") (pintype "bidirectional"))
    )
    (net (code "136") (name "unconnected-(BUFFER-3A-B5-Pad14)") (class "Default")
      (node (ref "BUFFER-3") (pin "14") (pinfunction "B5_14") (pintype "bidirectional"))
    )
    (net (code "137") (name "unconnected-(BUFFER-3A-B6-Pad13)") (class "Default")
      (node (ref "BUFFER-3") (pin "13") (pinfunction "B6_13") (pintype "bidirectional"))
    )
    (net (code "138") (name "unconnected-(BUFFER-3A-B7-Pad12)") (class "Default")
      (node (ref "BUFFER-3") (pin "12") (pinfunction "B7_12") (pintype "bidirectional"))
    )
    (net (code "139") (name "unconnected-(BUFFER-3A-B8-Pad11)") (class "Default")
      (node (ref "BUFFER-3") (pin "11") (pinfunction "B8_11") (pintype "bidirectional"))
    )
    (net (code "140") (name "unconnected-(MEMORY-0-8KX8-6264-NC-Pad1)") (class "Default")
      (node (ref "MEMORY-0-8KX8-6264") (pin "1") (pinfunction "NC_1") (pintype "no_connect"))
    )
    (net (code "141") (name "unconnected-(MEMORY-1-8KX8-6264-NC-Pad1)") (class "Default")
      (node (ref "MEMORY-1-8KX8-6264") (pin "1") (pinfunction "NC_1") (pintype "no_connect"))
    )
    (net (code "142") (name "unconnected-(MEMORY-2-8KX8-6264-NC-Pad1)") (class "Default")
      (node (ref "MEMORY-2-8KX8-6264") (pin "1") (pinfunction "NC_1") (pintype "no_connect"))
    )
    (net (code "143") (name "unconnected-(MEMORY-3-8KX8-6264-NC-Pad1)") (class "Default")
      (node (ref "MEMORY-3-8KX8-6264") (pin "1") (pinfunction "NC_1") (pintype "no_connect"))
    )
  )
)
